# 80PIN_FMU_REV_1A.net
KiCad netlist of a schematic drawn in Altium Designer
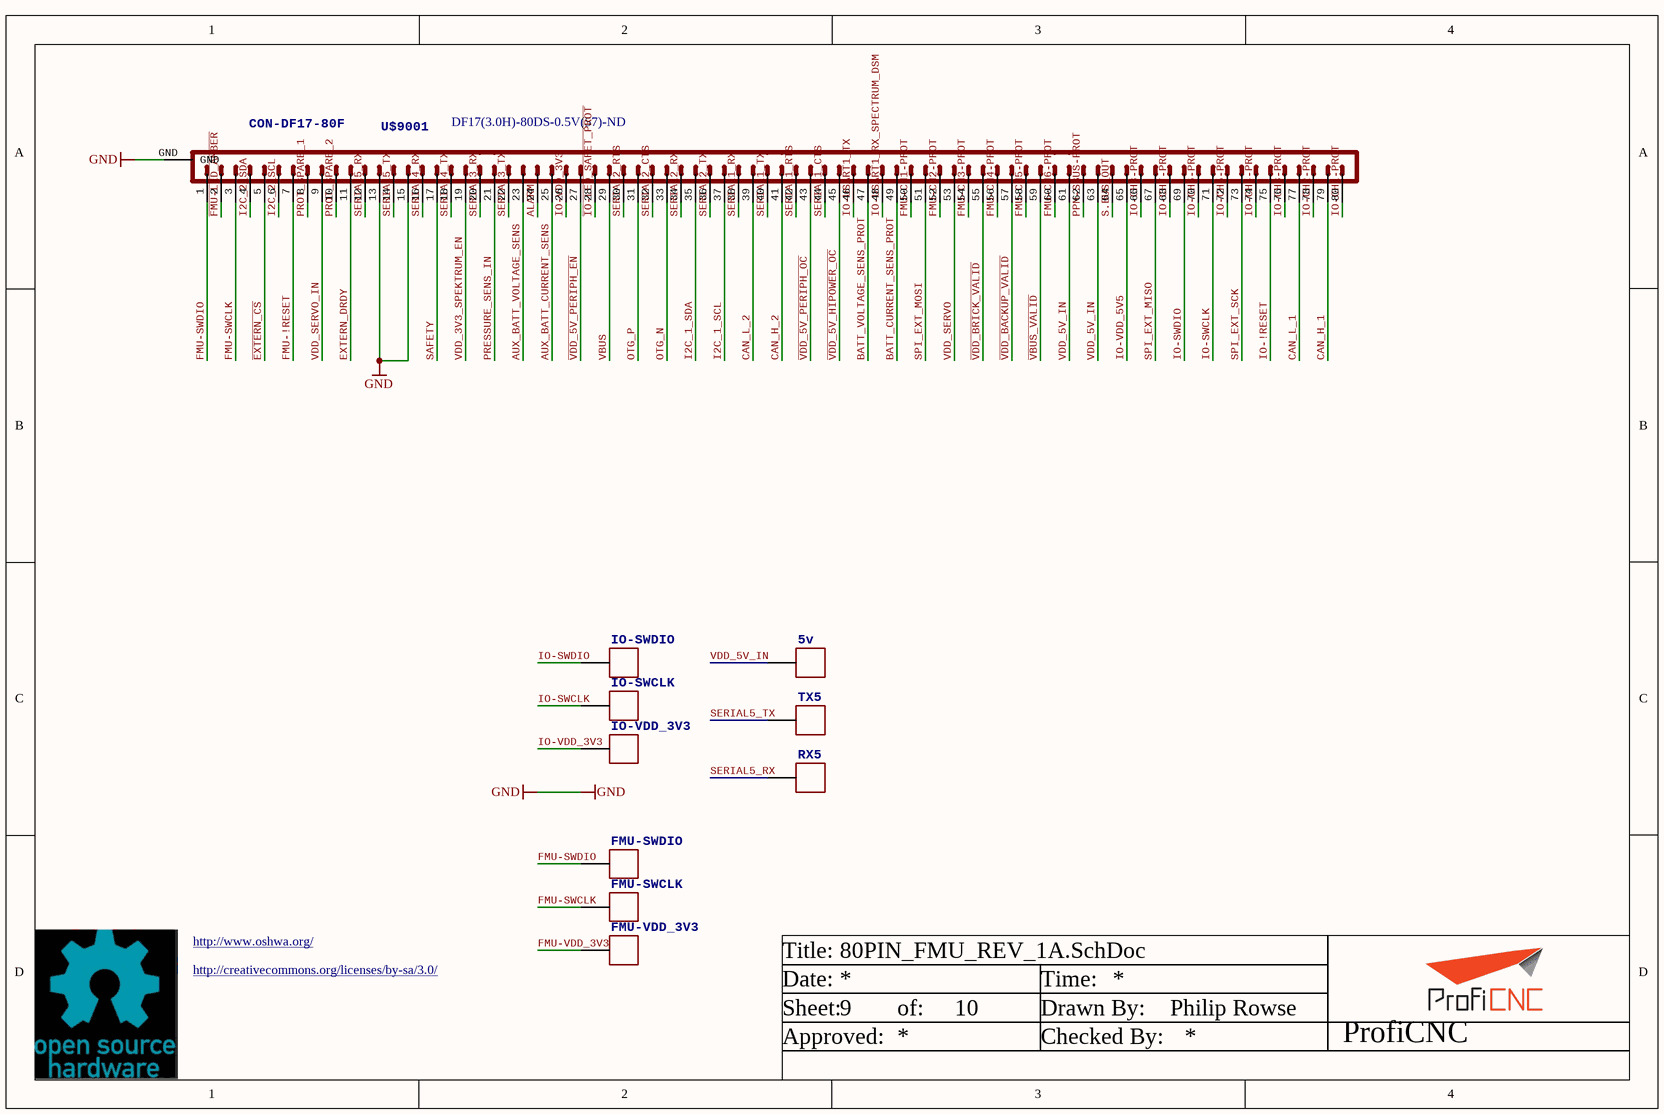
[diagram p0: 80PIN_FMU_REV_1A.SchDoc]

(export (version "E")
  (design (tool "Eeschema 10.0.6"))
  (components
    (comp (ref "5v") (value "PAD.04") (footprint "PAD.04X.04") (libsource (lib "pixhawk2") (part "PAD.04")))
    (comp (ref "FMU-SWCLK")
      (value "PAD.04")
      (footprint "PAD.04X.04")
      (libsource (lib "pixhawk2") (part "PAD.04"))
    )
    (comp (ref "FMU-SWDIO")
      (value "PAD.04")
      (footprint "PAD.04X.04")
      (libsource (lib "pixhawk2") (part "PAD.04"))
    )
    (comp (ref "FMU-VDD_3V3")
      (value "PAD.04")
      (footprint "PAD.04X.04")
      (libsource (lib "pixhawk2") (part "PAD.04"))
    )
    (comp (ref "IO-SWCLK")
      (value "PAD.04")
      (footprint "PAD.04X.04")
      (libsource (lib "pixhawk2") (part "PAD.04"))
    )
    (comp (ref "IO-SWDIO")
      (value "PAD.04")
      (footprint "PAD.04X.04")
      (libsource (lib "pixhawk2") (part "PAD.04"))
    )
    (comp (ref "IO-VDD_3V3")
      (value "PAD.04")
      (footprint "PAD.04X.04")
      (libsource (lib "pixhawk2") (part "PAD.04"))
    )
    (comp (ref "RX5") (value "PAD.04") (footprint "PAD.04X.04") (libsource (lib "pixhawk2") (part "PAD.04")))
    (comp (ref "TX5") (value "PAD.04") (footprint "PAD.04X.04") (libsource (lib "pixhawk2") (part "PAD.04")))
    (comp (ref "U$9001")
      (value "CON-DF17-80F")
      (footprint "CON-DF17-80F")
      (description "CONN RECEPT 80POS .5MM SMD W/FIT")
      (fields
        (field (name "SUPPLIER PART NUMBER 1") "DF17(3.0H)-80DS-0.5V(57)-ND")
        (field (name "3DR_PARTNO") "ECM0518")
        (field (name "PARTNO") "DF17(3.0H)-80DS-0.5V(57)")
      )
      (libsource (lib "pixhawk2") (part "CON-DF17-80F"))
    )
  )
  (nets
    (net (code "1") (name "/ALARM") (class "Default")
      (node (ref "U$9001") (pin "24") (pinfunction "24_24") (pintype "passive"))
    )
    (net (code "2") (name "/AUX_BATT_CURRENT_SENS") (class "Default")
      (node (ref "U$9001") (pin "25") (pinfunction "25_25") (pintype "passive"))
    )
    (net (code "3") (name "/AUX_BATT_VOLTAGE_SENS") (class "Default")
      (node (ref "U$9001") (pin "23") (pinfunction "23_23") (pintype "passive"))
    )
    (net (code "4") (name "/BATT_CURRENT_SENS_PROT") (class "Default")
      (node (ref "U$9001") (pin "49") (pinfunction "49_49") (pintype "passive"))
    )
    (net (code "5") (name "/BATT_VOLTAGE_SENS_PROT") (class "Default")
      (node (ref "U$9001") (pin "47") (pinfunction "47_47") (pintype "passive"))
    )
    (net (code "6") (name "/CAN_H_1") (class "Default")
      (node (ref "U$9001") (pin "79") (pinfunction "79_79") (pintype "passive"))
    )
    (net (code "7") (name "/CAN_H_2") (class "Default")
      (node (ref "U$9001") (pin "41") (pinfunction "41_41") (pintype "passive"))
    )
    (net (code "8") (name "/CAN_L_1") (class "Default")
      (node (ref "U$9001") (pin "77") (pinfunction "77_77") (pintype "passive"))
    )
    (net (code "9") (name "/CAN_L_2") (class "Default")
      (node (ref "U$9001") (pin "39") (pinfunction "39_39") (pintype "passive"))
    )
    (net (code "10") (name "/EXTERN_DRDY") (class "Default")
      (node (ref "U$9001") (pin "11") (pinfunction "11_11") (pintype "passive"))
    )
    (net (code "11") (name "/FMU-!RESET") (class "Default")
      (node (ref "U$9001") (pin "7") (pinfunction "7_7") (pintype "passive"))
    )
    (net (code "12") (name "/FMU-CH1-PROT") (class "Default")
      (node (ref "U$9001") (pin "50") (pinfunction "50_50") (pintype "passive"))
    )
    (net (code "13") (name "/FMU-CH2-PROT") (class "Default")
      (node (ref "U$9001") (pin "52") (pinfunction "52_52") (pintype "passive"))
    )
    (net (code "14") (name "/FMU-CH3-PROT") (class "Default")
      (node (ref "U$9001") (pin "54") (pinfunction "54_54") (pintype "passive"))
    )
    (net (code "15") (name "/FMU-CH4-PROT") (class "Default")
      (node (ref "U$9001") (pin "56") (pinfunction "56_56") (pintype "passive"))
    )
    (net (code "16") (name "/FMU-CH5-PROT") (class "Default")
      (node (ref "U$9001") (pin "58") (pinfunction "58_58") (pintype "passive"))
    )
    (net (code "17") (name "/FMU-CH6-PROT") (class "Default")
      (node (ref "U$9001") (pin "60") (pinfunction "60_60") (pintype "passive"))
    )
    (net (code "18") (name "/FMU-SWCLK") (class "Default")
      (node (ref "FMU-SWCLK") (pin "P$1") (pinfunction "P$1_P$1") (pintype "passive"))
      (node (ref "U$9001") (pin "3") (pinfunction "3_3") (pintype "passive"))
    )
    (net (code "19") (name "/FMU-SWDIO") (class "Default")
      (node (ref "FMU-SWDIO") (pin "P$1") (pinfunction "P$1_P$1") (pintype "passive"))
      (node (ref "U$9001") (pin "1") (pinfunction "1_1") (pintype "passive"))
    )
    (net (code "20") (name "/FMU-VDD_3V3") (class "Default")
      (node (ref "FMU-VDD_3V3") (pin "P$1") (pinfunction "P$1_P$1") (pintype "passive"))
    )
    (net (code "21") (name "/I2C_1_SCL") (class "Default")
      (node (ref "U$9001") (pin "37") (pinfunction "37_37") (pintype "passive"))
    )
    (net (code "22") (name "/I2C_1_SDA") (class "Default")
      (node (ref "U$9001") (pin "35") (pinfunction "35_35") (pintype "passive"))
    )
    (net (code "23") (name "/I2C_2_SCL") (class "Default")
      (node (ref "U$9001") (pin "6") (pinfunction "6_6") (pintype "passive"))
    )
    (net (code "24") (name "/I2C_2_SDA") (class "Default")
      (node (ref "U$9001") (pin "4") (pinfunction "4_4") (pintype "passive"))
    )
    (net (code "25") (name "/IO-!RESET") (class "Default")
      (node (ref "U$9001") (pin "75") (pinfunction "75_75") (pintype "passive"))
    )
    (net (code "26") (name "/IO-CH1-PROT") (class "Default")
      (node (ref "U$9001") (pin "80") (pinfunction "80_80") (pintype "passive"))
    )
    (net (code "27") (name "/IO-CH2-PROT") (class "Default")
      (node (ref "U$9001") (pin "78") (pinfunction "78_78") (pintype "passive"))
    )
    (net (code "28") (name "/IO-CH3-PROT") (class "Default")
      (node (ref "U$9001") (pin "76") (pinfunction "76_76") (pintype "passive"))
    )
    (net (code "29") (name "/IO-CH4-PROT") (class "Default")
      (node (ref "U$9001") (pin "74") (pinfunction "74_74") (pintype "passive"))
    )
    (net (code "30") (name "/IO-CH5-PROT") (class "Default")
      (node (ref "U$9001") (pin "72") (pinfunction "72_72") (pintype "passive"))
    )
    (net (code "31") (name "/IO-CH6-PROT") (class "Default")
      (node (ref "U$9001") (pin "70") (pinfunction "70_70") (pintype "passive"))
    )
    (net (code "32") (name "/IO-CH7-PROT") (class "Default")
      (node (ref "U$9001") (pin "68") (pinfunction "68_68") (pintype "passive"))
    )
    (net (code "33") (name "/IO-CH8-PROT") (class "Default")
      (node (ref "U$9001") (pin "66") (pinfunction "66_66") (pintype "passive"))
    )
    (net (code "34") (name "/IO-SWCLK") (class "Default")
      (node (ref "IO-SWCLK") (pin "P$1") (pinfunction "P$1_P$1") (pintype "passive"))
      (node (ref "U$9001") (pin "71") (pinfunction "71_71") (pintype "passive"))
    )
    (net (code "35") (name "/IO-SWDIO") (class "Default")
      (node (ref "IO-SWDIO") (pin "P$1") (pinfunction "P$1_P$1") (pintype "passive"))
      (node (ref "U$9001") (pin "69") (pinfunction "69_69") (pintype "passive"))
    )
    (net (code "36") (name "/IO-USART1_RX_SPECTRUM_DSM") (class "Default")
      (node (ref "U$9001") (pin "48") (pinfunction "48_48") (pintype "passive"))
    )
    (net (code "37") (name "/IO-USART1_TX") (class "Default")
      (node (ref "U$9001") (pin "46") (pinfunction "46_46") (pintype "passive"))
    )
    (net (code "38") (name "/IO-VDD_3V3") (class "Default")
      (node (ref "IO-VDD_3V3") (pin "P$1") (pinfunction "P$1_P$1") (pintype "passive"))
      (node (ref "U$9001") (pin "26") (pinfunction "26_26") (pintype "passive"))
    )
    (net (code "39") (name "/IO-VDD_5V5") (class "Default")
      (node (ref "U$9001") (pin "65") (pinfunction "65_65") (pintype "passive"))
    )
    (net (code "40") (name "/OTG_N") (class "Default")
      (node (ref "U$9001") (pin "33") (pinfunction "33_33") (pintype "passive"))
    )
    (net (code "41") (name "/OTG_P") (class "Default")
      (node (ref "U$9001") (pin "31") (pinfunction "31_31") (pintype "passive"))
    )
    (net (code "42") (name "/PPM-SBUS-PROT") (class "Default")
      (node (ref "U$9001") (pin "62") (pinfunction "62_62") (pintype "passive"))
    )
    (net (code "43") (name "/PRESSURE_SENS_IN") (class "Default")
      (node (ref "U$9001") (pin "21") (pinfunction "21_21") (pintype "passive"))
    )
    (net (code "44") (name "/PROT_SPARE_1") (class "Default")
      (node (ref "U$9001") (pin "8") (pinfunction "8_8") (pintype "passive"))
    )
    (net (code "45") (name "/PROT_SPARE_2") (class "Default")
      (node (ref "U$9001") (pin "10") (pinfunction "10_10") (pintype "passive"))
    )
    (net (code "46") (name "/S.BUS_OUT") (class "Default")
      (node (ref "U$9001") (pin "64") (pinfunction "64_64") (pintype "passive"))
    )
    (net (code "47") (name "/SAFETY") (class "Default")
      (node (ref "U$9001") (pin "17") (pinfunction "17_17") (pintype "passive"))
    )
    (net (code "48") (name "/SERIAL1_CTS") (class "Default")
      (node (ref "U$9001") (pin "44") (pinfunction "44_44") (pintype "passive"))
    )
    (net (code "49") (name "/SERIAL1_RTS") (class "Default")
      (node (ref "U$9001") (pin "42") (pinfunction "42_42") (pintype "passive"))
    )
    (net (code "50") (name "/SERIAL1_RX") (class "Default")
      (node (ref "U$9001") (pin "38") (pinfunction "38_38") (pintype "passive"))
    )
    (net (code "51") (name "/SERIAL1_TX") (class "Default")
      (node (ref "U$9001") (pin "40") (pinfunction "40_40") (pintype "passive"))
    )
    (net (code "52") (name "/SERIAL2_CTS") (class "Default")
      (node (ref "U$9001") (pin "32") (pinfunction "32_32") (pintype "passive"))
    )
    (net (code "53") (name "/SERIAL2_RTS") (class "Default")
      (node (ref "U$9001") (pin "30") (pinfunction "30_30") (pintype "passive"))
    )
    (net (code "54") (name "/SERIAL2_RX") (class "Default")
      (node (ref "U$9001") (pin "34") (pinfunction "34_34") (pintype "passive"))
    )
    (net (code "55") (name "/SERIAL2_TX") (class "Default")
      (node (ref "U$9001") (pin "36") (pinfunction "36_36") (pintype "passive"))
    )
    (net (code "56") (name "/SERIAL3_RX") (class "Default")
      (node (ref "U$9001") (pin "20") (pinfunction "20_20") (pintype "passive"))
    )
    (net (code "57") (name "/SERIAL3_TX") (class "Default")
      (node (ref "U$9001") (pin "22") (pinfunction "22_22") (pintype "passive"))
    )
    (net (code "58") (name "/SERIAL4_RX") (class "Default")
      (node (ref "U$9001") (pin "16") (pinfunction "16_16") (pintype "passive"))
    )
    (net (code "59") (name "/SERIAL4_TX") (class "Default")
      (node (ref "U$9001") (pin "18") (pinfunction "18_18") (pintype "passive"))
    )
    (net (code "60") (name "/SERIAL5_RX") (class "Default")
      (node (ref "RX5") (pin "P$1") (pinfunction "P$1_P$1") (pintype "passive"))
      (node (ref "U$9001") (pin "12") (pinfunction "12_12") (pintype "passive"))
    )
    (net (code "61") (name "/SERIAL5_TX") (class "Default")
      (node (ref "TX5") (pin "P$1") (pinfunction "P$1_P$1") (pintype "passive"))
      (node (ref "U$9001") (pin "14") (pinfunction "14_14") (pintype "passive"))
    )
    (net (code "62") (name "/SPI_EXT_MISO") (class "Default")
      (node (ref "U$9001") (pin "67") (pinfunction "67_67") (pintype "passive"))
    )
    (net (code "63") (name "/SPI_EXT_MOSI") (class "Default")
      (node (ref "U$9001") (pin "51") (pinfunction "51_51") (pintype "passive"))
    )
    (net (code "64") (name "/SPI_EXT_SCK") (class "Default")
      (node (ref "U$9001") (pin "73") (pinfunction "73_73") (pintype "passive"))
    )
    (net (code "65") (name "/VBUS") (class "Default")
      (node (ref "U$9001") (pin "29") (pinfunction "29_29") (pintype "passive"))
    )
    (net (code "66") (name "/VDD_3V3_SPEKTRUM_EN") (class "Default")
      (node (ref "U$9001") (pin "19") (pinfunction "19_19") (pintype "passive"))
    )
    (net (code "67") (name "/VDD_5V_IN") (class "Default")
      (node (ref "5v") (pin "P$1") (pinfunction "P$1_P$1") (pintype "passive"))
      (node (ref "U$9001") (pin "61") (pinfunction "61_61") (pintype "passive"))
      (node (ref "U$9001") (pin "63") (pinfunction "63_63") (pintype "passive"))
    )
    (net (code "68") (name "/VDD_SERVO") (class "Default")
      (node (ref "U$9001") (pin "53") (pinfunction "53_53") (pintype "passive"))
    )
    (net (code "69") (name "/VDD_SERVO_IN") (class "Default")
      (node (ref "U$9001") (pin "9") (pinfunction "9_9") (pintype "passive"))
    )
    (net (code "70") (name "/~{EXTERN_CS}") (class "Default")
      (node (ref "U$9001") (pin "5") (pinfunction "5_5") (pintype "passive"))
    )
    (net (code "71") (name "/~{FMU-LED_AMBER}") (class "Default")
      (node (ref "U$9001") (pin "2") (pinfunction "2_2") (pintype "passive"))
    )
    (net (code "72") (name "/~{IO-LED_SAFET_PROT}") (class "Default")
      (node (ref "U$9001") (pin "28") (pinfunction "28_28") (pintype "passive"))
    )
    (net (code "73") (name "/~{VBUS_VALID}") (class "Default")
      (node (ref "U$9001") (pin "59") (pinfunction "59_59") (pintype "passive"))
    )
    (net (code "74") (name "/~{VDD_5V_HIPOWER_OC}") (class "Default")
      (node (ref "U$9001") (pin "45") (pinfunction "45_45") (pintype "passive"))
    )
    (net (code "75") (name "/~{VDD_5V_PERIPH_EN}") (class "Default")
      (node (ref "U$9001") (pin "27") (pinfunction "27_27") (pintype "passive"))
    )
    (net (code "76") (name "/~{VDD_5V_PERIPH_OC}") (class "Default")
      (node (ref "U$9001") (pin "43") (pinfunction "43_43") (pintype "passive"))
    )
    (net (code "77") (name "/~{VDD_BACKUP_VALID}") (class "Default")
      (node (ref "U$9001") (pin "57") (pinfunction "57_57") (pintype "passive"))
    )
    (net (code "78") (name "/~{VDD_BRICK_VALID}") (class "Default")
      (node (ref "U$9001") (pin "55") (pinfunction "55_55") (pintype "passive"))
    )
    (net (code "79") (name "GND") (class "Default")
      (node (ref "U$9001") (pin "13") (pinfunction "13_13") (pintype "passive"))
      (node (ref "U$9001") (pin "15") (pinfunction "15_15") (pintype "passive"))
      (node (ref "U$9001") (pin "GND") (pinfunction "GND_GND") (pintype "passive"))
    )
  )
)
